# BBB_Headers.net
KiCad netlist of a schematic drawn in Altium Designer
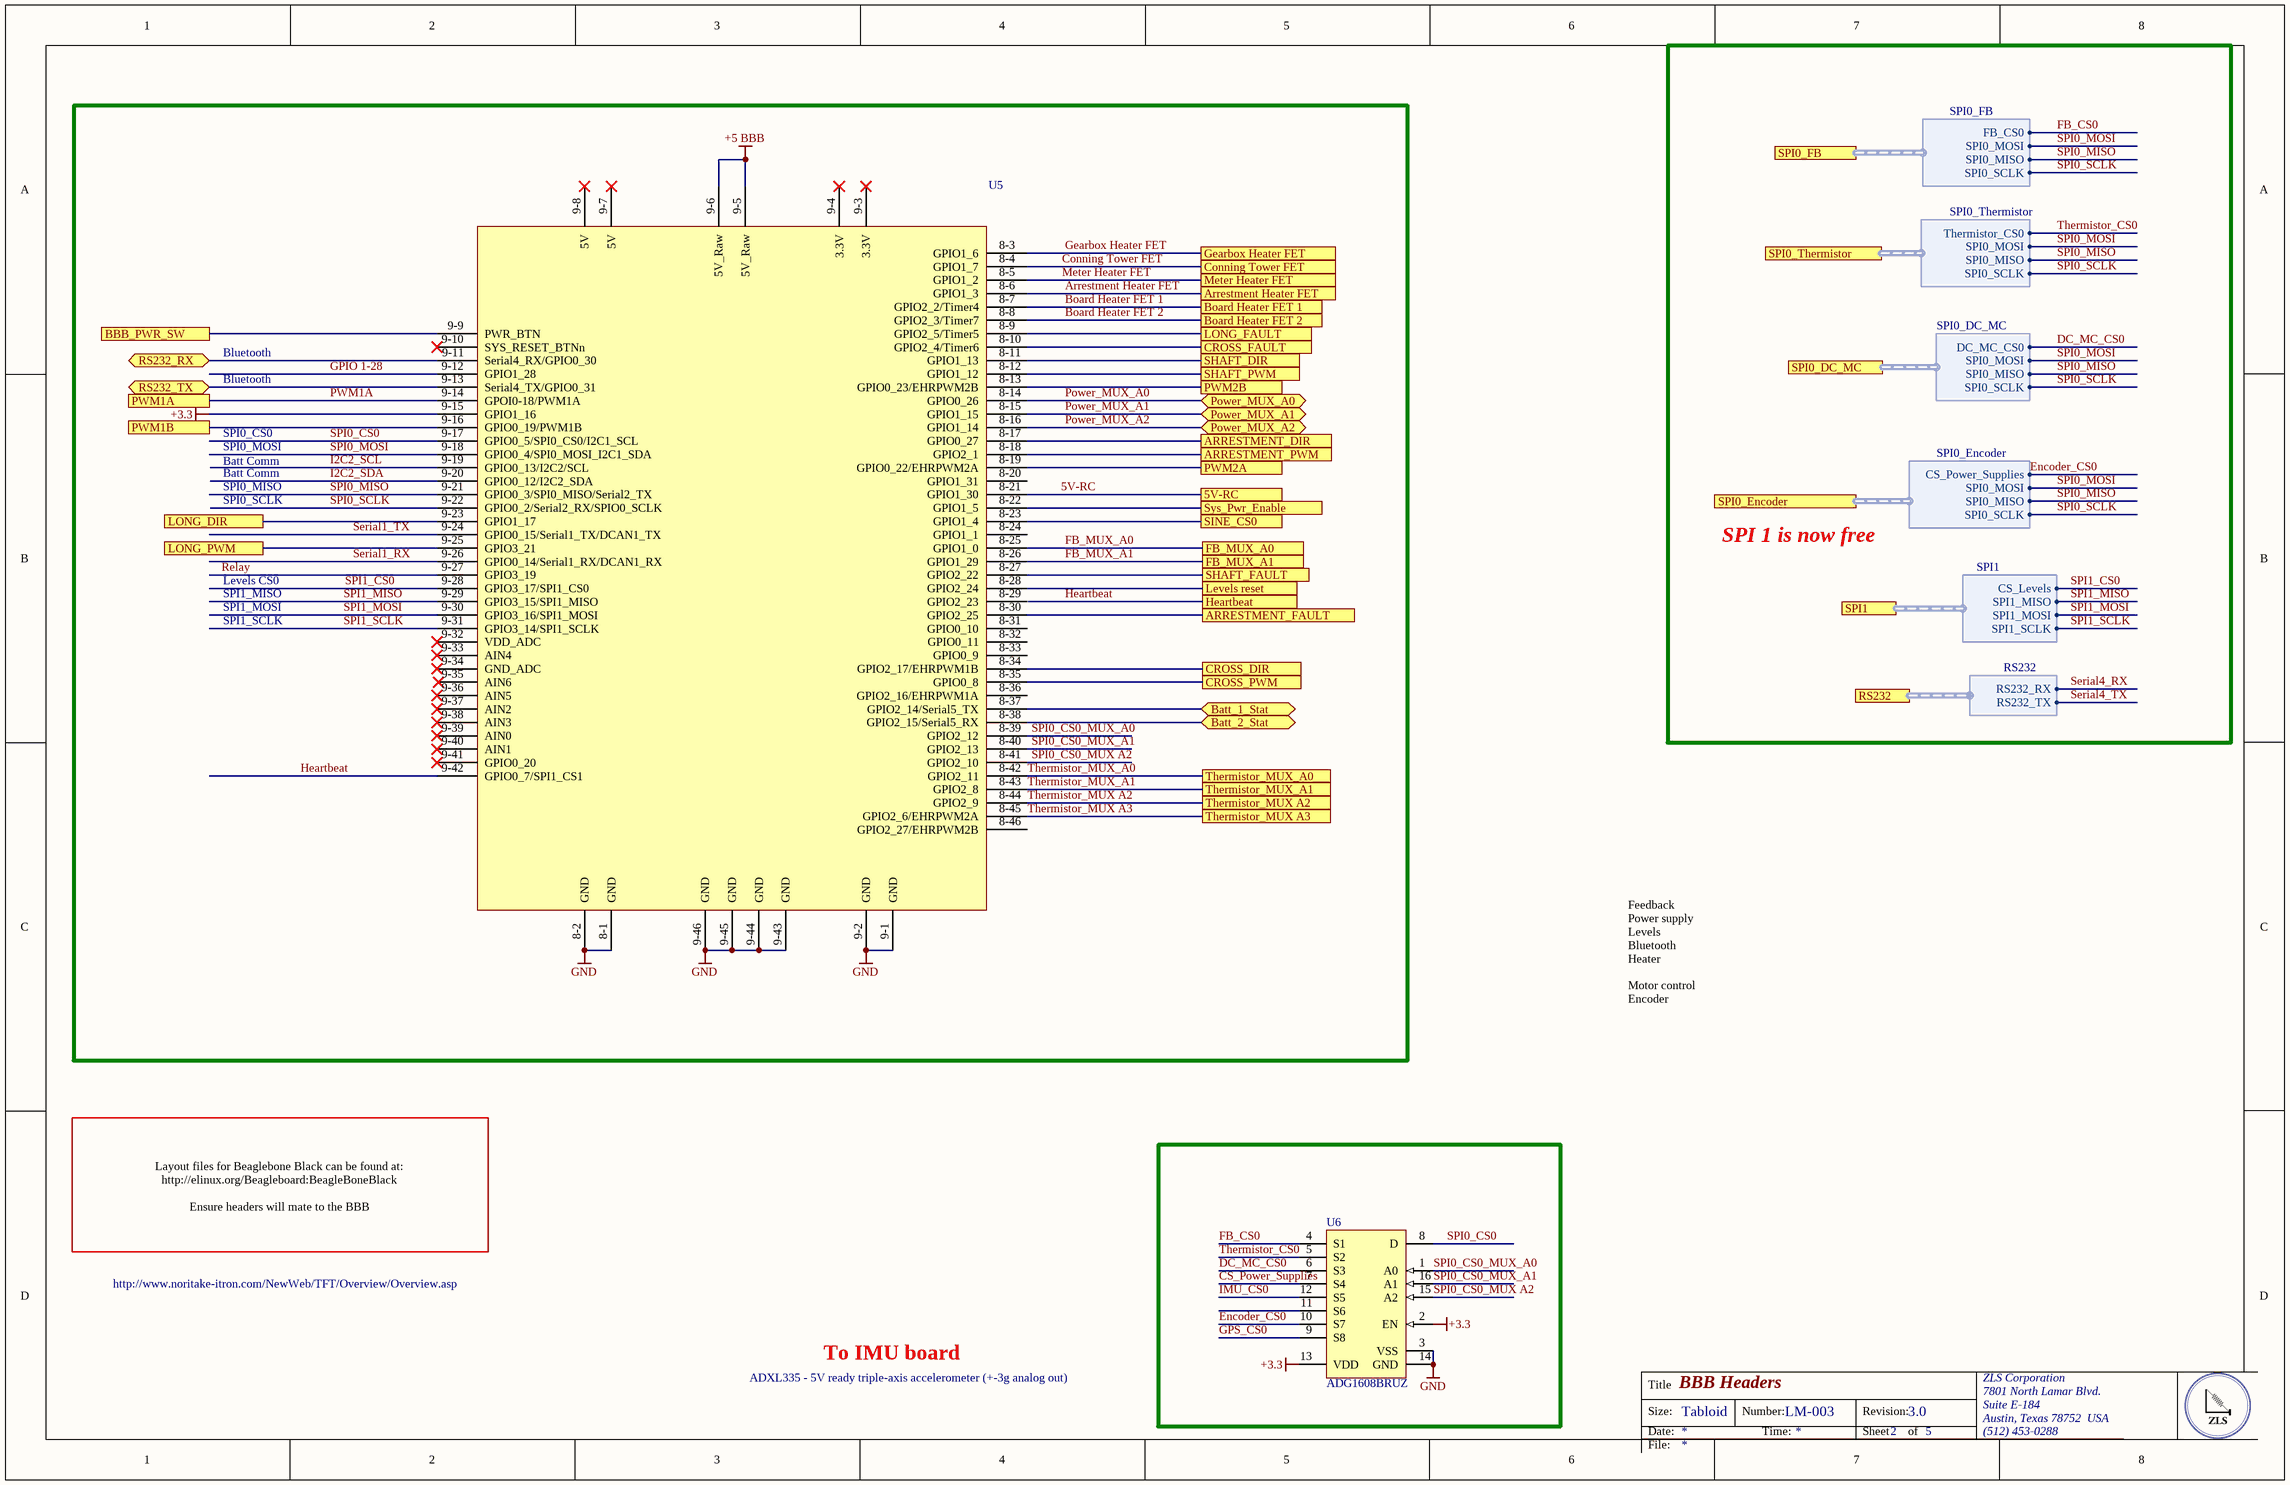
[diagram p0: BBB Headers.SchDoc]

(export (version "E")
  (design (tool "Eeschema 10.0.6"))
  (components
    (comp (ref "U5")
      (value "BBB")
      (footprint "Beaglebone Black")
      (description "Beaglebone Black")
      (fields
        (field (name "MANUFACTURER") "Molex, LLC")
        (field (name "MANUFACTURER PART NUMBER") "0010897462")
      )
      (libsource (lib "ZLS_Schematic_lib") (part "Beaglebone_Black"))
    )
    (comp (ref "U6")
      (value "ADG1608BRUZ")
      (footprint "ADI-RU-16_M")
      (description "4.5 Ohm Ron, 8-Channel +/-5 V,+12 V, +5 V and +3.3 V Multiplexer, 16-pin SOP (RU-16), Tube")
      (fields (field (name "MANUFACTURER") "Analog Devices"))
      (libsource (lib "Altium Content Vault") (part "ADI-ADG1608-RU-16"))
    )
  )
  (nets
    (net (code "7") (name "+3.3") (class "Default")
      (node (ref "U5") (pin "9-15") (pinfunction "GPIO1_16_9-15") (pintype "passive"))
      (node (ref "U6") (pin "13") (pinfunction "VDD_13") (pintype "power_in"))
      (node (ref "U6") (pin "2") (pinfunction "EN_2") (pintype "input"))
    )
    (net (code "8") (name "+5 BBB") (class "Default")
      (node (ref "U5") (pin "9-5") (pinfunction "5V_Raw_9-5") (pintype "passive"))
      (node (ref "U5") (pin "9-6") (pinfunction "5V_Raw_9-6") (pintype "passive"))
    )
    (net (code "9") (name "/5V-RC") (class "Default")
      (node (ref "U5") (pin "8-21") (pinfunction "GPIO1_30_8-21") (pintype "passive"))
    )
    (net (code "10") (name "/ARRESTMENT_DIR") (class "Default")
      (node (ref "U5") (pin "8-17") (pinfunction "GPIO0_27_8-17") (pintype "passive"))
    )
    (net (code "11") (name "/ARRESTMENT_FAULT") (class "Default")
      (node (ref "U5") (pin "8-30") (pinfunction "GPIO2_25_8-30") (pintype "passive"))
    )
    (net (code "12") (name "/ARRESTMENT_PWM") (class "Default")
      (node (ref "U5") (pin "8-18") (pinfunction "GPIO2_1_8-18") (pintype "passive"))
    )
    (net (code "13") (name "/Arrestment Heater FET") (class "Default")
      (node (ref "U5") (pin "8-6") (pinfunction "GPIO1_3_8-6") (pintype "passive"))
    )
    (net (code "14") (name "/BBB_PWR_SW") (class "Default")
      (node (ref "U5") (pin "9-9") (pinfunction "PWR_BTN_9-9") (pintype "passive"))
    )
    (net (code "15") (name "/Batt_1_Stat") (class "Default")
      (node (ref "U5") (pin "8-37") (pinfunction "GPIO2_14/Serial5_TX_8-37") (pintype "passive"))
    )
    (net (code "16") (name "/Batt_2_Stat") (class "Default")
      (node (ref "U5") (pin "8-38") (pinfunction "GPIO2_15/Serial5_RX_8-38") (pintype "passive"))
    )
    (net (code "17") (name "/Board Heater FET 1") (class "Default")
      (node (ref "U5") (pin "8-7") (pinfunction "GPIO2_2/Timer4_8-7") (pintype "passive"))
    )
    (net (code "18") (name "/Board Heater FET 2") (class "Default")
      (node (ref "U5") (pin "8-8") (pinfunction "GPIO2_3/Timer7_8-8") (pintype "passive"))
    )
    (net (code "19") (name "/CROSS_DIR") (class "Default")
      (node (ref "U5") (pin "8-34") (pinfunction "GPIO2_17/EHRPWM1B_8-34") (pintype "passive"))
    )
    (net (code "20") (name "/CROSS_FAULT") (class "Default")
      (node (ref "U5") (pin "8-10") (pinfunction "GPIO2_4/Timer6_8-10") (pintype "passive"))
    )
    (net (code "21") (name "/CROSS_PWM") (class "Default")
      (node (ref "U5") (pin "8-35") (pinfunction "GPIO0_8_8-35") (pintype "passive"))
    )
    (net (code "22") (name "/CS_Power_Supplies") (class "Default")
      (node (ref "U6") (pin "7") (pinfunction "S4_7") (pintype "passive"))
    )
    (net (code "23") (name "/Conning Tower FET") (class "Default")
      (node (ref "U5") (pin "8-4") (pinfunction "GPIO1_7_8-4") (pintype "passive"))
    )
    (net (code "24") (name "/DC_MC_CS0") (class "Default")
      (node (ref "U6") (pin "6") (pinfunction "S3_6") (pintype "passive"))
    )
    (net (code "25") (name "/Encoder_CS0") (class "Default")
      (node (ref "U6") (pin "10") (pinfunction "S7_10") (pintype "passive"))
    )
    (net (code "26") (name "/FB_CS0") (class "Default")
      (node (ref "U6") (pin "4") (pinfunction "S1_4") (pintype "passive"))
    )
    (net (code "27") (name "/FB_MUX_A0") (class "Default")
      (node (ref "U5") (pin "8-25") (pinfunction "GPIO1_0_8-25") (pintype "passive"))
    )
    (net (code "28") (name "/FB_MUX_A1") (class "Default")
      (node (ref "U5") (pin "8-26") (pinfunction "GPIO1_29_8-26") (pintype "passive"))
    )
    (net (code "29") (name "/GPIO 1-28") (class "Default")
      (node (ref "U5") (pin "9-12") (pinfunction "GPIO1_28_9-12") (pintype "passive"))
    )
    (net (code "30") (name "/GPS_CS0") (class "Default")
      (node (ref "U6") (pin "9") (pinfunction "S8_9") (pintype "passive"))
    )
    (net (code "31") (name "/Gearbox Heater FET") (class "Default")
      (node (ref "U5") (pin "8-3") (pinfunction "GPIO1_6_8-3") (pintype "passive"))
    )
    (net (code "32") (name "/Heartbeat") (class "Default")
      (node (ref "U5") (pin "9-42") (pinfunction "GPIO0_7/SPI1_CS1_9-42") (pintype "passive"))
    )
    (net (code "33") (name "/I2C2_SCL") (class "Default")
      (node (ref "U5") (pin "9-19") (pinfunction "GPIO0_13/I2C2/SCL_9-19") (pintype "passive"))
    )
    (net (code "34") (name "/I2C2_SDA") (class "Default")
      (node (ref "U5") (pin "9-20") (pinfunction "GPIO0_12/I2C2_SDA_9-20") (pintype "passive"))
    )
    (net (code "35") (name "/IMU_CS0") (class "Default")
      (node (ref "U6") (pin "12") (pinfunction "S5_12") (pintype "passive"))
    )
    (net (code "36") (name "/LONG_DIR") (class "Default")
      (node (ref "U5") (pin "9-23") (pinfunction "GPIO1_17_9-23") (pintype "passive"))
    )
    (net (code "37") (name "/LONG_FAULT") (class "Default")
      (node (ref "U5") (pin "8-9") (pinfunction "GPIO2_5/Timer5_8-9") (pintype "passive"))
    )
    (net (code "38") (name "/LONG_PWM") (class "Default")
      (node (ref "U5") (pin "9-25") (pinfunction "GPIO3_21_9-25") (pintype "passive"))
    )
    (net (code "39") (name "/Levels reset") (class "Default")
      (node (ref "U5") (pin "8-28") (pinfunction "GPIO2_24_8-28") (pintype "passive"))
    )
    (net (code "40") (name "/Meter Heater FET") (class "Default")
      (node (ref "U5") (pin "8-5") (pinfunction "GPIO1_2_8-5") (pintype "passive"))
    )
    (net (code "41") (name "/PWM1A") (class "Default")
      (node (ref "U5") (pin "9-14") (pinfunction "GPOI0-18/PWM1A_9-14") (pintype "passive"))
    )
    (net (code "42") (name "/PWM1B") (class "Default")
      (node (ref "U5") (pin "9-16") (pinfunction "GPIO0_19/PWM1B_9-16") (pintype "passive"))
    )
    (net (code "43") (name "/PWM2A") (class "Default")
      (node (ref "U5") (pin "8-19") (pinfunction "GPIO0_22/EHRPWM2A_8-19") (pintype "passive"))
    )
    (net (code "44") (name "/PWM2B") (class "Default")
      (node (ref "U5") (pin "8-13") (pinfunction "GPIO0_23/EHRPWM2B_8-13") (pintype "passive"))
    )
    (net (code "45") (name "/Power_MUX_A0") (class "Default")
      (node (ref "U5") (pin "8-14") (pinfunction "GPIO0_26_8-14") (pintype "passive"))
    )
    (net (code "46") (name "/Power_MUX_A1") (class "Default")
      (node (ref "U5") (pin "8-15") (pinfunction "GPIO1_15_8-15") (pintype "passive"))
    )
    (net (code "47") (name "/Power_MUX_A2") (class "Default")
      (node (ref "U5") (pin "8-16") (pinfunction "GPIO1_14_8-16") (pintype "passive"))
    )
    (net (code "48") (name "/RS232_RX") (class "Default")
      (node (ref "U5") (pin "9-11") (pinfunction "Serial4_RX/GPIO0_30_9-11") (pintype "passive"))
    )
    (net (code "49") (name "/RS232_TX") (class "Default")
      (node (ref "U5") (pin "9-13") (pinfunction "Serial4_TX/GPIO0_31_9-13") (pintype "passive"))
    )
    (net (code "50") (name "/Relay") (class "Default")
      (node (ref "U5") (pin "9-27") (pinfunction "GPIO3_19_9-27") (pintype "passive"))
    )
    (net (code "51") (name "/SHAFT_DIR") (class "Default")
      (node (ref "U5") (pin "8-11") (pinfunction "GPIO1_13_8-11") (pintype "passive"))
    )
    (net (code "52") (name "/SHAFT_FAULT") (class "Default")
      (node (ref "U5") (pin "8-27") (pinfunction "GPIO2_22_8-27") (pintype "passive"))
    )
    (net (code "53") (name "/SHAFT_PWM") (class "Default")
      (node (ref "U5") (pin "8-12") (pinfunction "GPIO1_12_8-12") (pintype "passive"))
    )
    (net (code "54") (name "/SINE_CS0") (class "Default")
      (node (ref "U5") (pin "8-23") (pinfunction "GPIO1_4_8-23") (pintype "passive"))
    )
    (net (code "55") (name "/SPI0_CS0") (class "Default")
      (node (ref "U5") (pin "9-17") (pinfunction "GPIO0_5/SPI0_CS0/I2C1_SCL_9-17") (pintype "passive"))
      (node (ref "U6") (pin "8") (pinfunction "D_8") (pintype "passive"))
    )
    (net (code "56") (name "/SPI0_CS0_MUX A2") (class "Default")
      (node (ref "U5") (pin "8-41") (pinfunction "GPIO2_10_8-41") (pintype "passive"))
      (node (ref "U6") (pin "15") (pinfunction "A2_15") (pintype "input"))
    )
    (net (code "57") (name "/SPI0_CS0_MUX_A0") (class "Default")
      (node (ref "U5") (pin "8-39") (pinfunction "GPIO2_12_8-39") (pintype "passive"))
      (node (ref "U6") (pin "1") (pinfunction "A0_1") (pintype "input"))
    )
    (net (code "58") (name "/SPI0_CS0_MUX_A1") (class "Default")
      (node (ref "U5") (pin "8-40") (pinfunction "GPIO2_13_8-40") (pintype "passive"))
      (node (ref "U6") (pin "16") (pinfunction "A1_16") (pintype "input"))
    )
    (net (code "59") (name "/SPI0_MISO") (class "Default")
      (node (ref "U5") (pin "9-21") (pinfunction "GPIO0_3/SPI0_MISO/Serial2_TX_9-21") (pintype "passive"))
    )
    (net (code "60") (name "/SPI0_MOSI") (class "Default")
      (node (ref "U5") (pin "9-18") (pinfunction "GPIO0_4/SPI0_MOSI_I2C1_SDA_9-18") (pintype "passive"))
    )
    (net (code "61") (name "/SPI0_SCLK") (class "Default")
      (node (ref "U5") (pin "9-22") (pinfunction "GPIO0_2/Serial2_RX/SPIO0_SCLK_9-22") (pintype "passive"))
    )
    (net (code "62") (name "/SPI1_CS0") (class "Default")
      (node (ref "U5") (pin "9-28") (pinfunction "GPIO3_17/SPI1_CS0_9-28") (pintype "passive"))
    )
    (net (code "63") (name "/SPI1_MISO") (class "Default")
      (node (ref "U5") (pin "9-29") (pinfunction "GPIO3_15/SPI1_MISO_9-29") (pintype "passive"))
    )
    (net (code "64") (name "/SPI1_MOSI") (class "Default")
      (node (ref "U5") (pin "9-30") (pinfunction "GPIO3_16/SPI1_MOSI_9-30") (pintype "passive"))
    )
    (net (code "65") (name "/SPI1_SCLK") (class "Default")
      (node (ref "U5") (pin "9-31") (pinfunction "GPIO3_14/SPI1_SCLK_9-31") (pintype "passive"))
    )
    (net (code "66") (name "/Serial1_RX") (class "Default")
      (node (ref "U5") (pin "9-26") (pinfunction "GPIO0_14/Serial1_RX/DCAN1_RX_9-26") (pintype "passive"))
    )
    (net (code "67") (name "/Serial1_TX") (class "Default")
      (node (ref "U5") (pin "9-24") (pinfunction "GPIO0_15/Serial1_TX/DCAN1_TX_9-24") (pintype "passive"))
    )
    (net (code "70") (name "/Sys_Pwr_Enable") (class "Default")
      (node (ref "U5") (pin "8-22") (pinfunction "GPIO1_5_8-22") (pintype "passive"))
    )
    (net (code "71") (name "/Thermistor_CS0") (class "Default")
      (node (ref "U6") (pin "5") (pinfunction "S2_5") (pintype "passive"))
    )
    (net (code "72") (name "/Thermistor_MUX A2") (class "Default")
      (node (ref "U5") (pin "8-44") (pinfunction "GPIO2_9_8-44") (pintype "passive"))
    )
    (net (code "73") (name "/Thermistor_MUX A3") (class "Default")
      (node (ref "U5") (pin "8-45") (pinfunction "GPIO2_6/EHRPWM2A_8-45") (pintype "passive"))
    )
    (net (code "74") (name "/Thermistor_MUX_A0") (class "Default")
      (node (ref "U5") (pin "8-42") (pinfunction "GPIO2_11_8-42") (pintype "passive"))
    )
    (net (code "75") (name "/Thermistor_MUX_A1") (class "Default")
      (node (ref "U5") (pin "8-43") (pinfunction "GPIO2_8_8-43") (pintype "passive"))
    )
    (net (code "82") (name "GND") (class "Default")
      (node (ref "U5") (pin "8-1") (pinfunction "GND_8-1") (pintype "passive"))
      (node (ref "U5") (pin "8-2") (pinfunction "GND_8-2") (pintype "passive"))
      (node (ref "U5") (pin "9-1") (pinfunction "GND_9-1") (pintype "passive"))
      (node (ref "U5") (pin "9-2") (pinfunction "GND_9-2") (pintype "passive"))
      (node (ref "U5") (pin "9-43") (pinfunction "GND_9-43") (pintype "passive"))
      (node (ref "U5") (pin "9-44") (pinfunction "GND_9-44") (pintype "passive"))
      (node (ref "U5") (pin "9-45") (pinfunction "GND_9-45") (pintype "passive"))
      (node (ref "U5") (pin "9-46") (pinfunction "GND_9-46") (pintype "passive"))
      (node (ref "U6") (pin "14") (pinfunction "GND_14") (pintype "power_in"))
      (node (ref "U6") (pin "3") (pinfunction "VSS_3") (pintype "power_in"))
    )
    (net (code "83") (name "unconnected-(U5-3.3V-Pad9-3)") (class "Default")
      (node (ref "U5") (pin "9-3") (pinfunction "3.3V_9-3") (pintype "passive+no_connect"))
    )
    (net (code "84") (name "unconnected-(U5-3.3V-Pad9-4)") (class "Default")
      (node (ref "U5") (pin "9-4") (pinfunction "3.3V_9-4") (pintype "passive+no_connect"))
    )
    (net (code "85") (name "unconnected-(U5-5V-Pad9-7)") (class "Default")
      (node (ref "U5") (pin "9-7") (pinfunction "5V_9-7") (pintype "passive+no_connect"))
    )
    (net (code "86") (name "unconnected-(U5-5V-Pad9-8)") (class "Default")
      (node (ref "U5") (pin "9-8") (pinfunction "5V_9-8") (pintype "passive+no_connect"))
    )
    (net (code "87") (name "unconnected-(U5-AIN0-Pad9-39)") (class "Default")
      (node (ref "U5") (pin "9-39") (pinfunction "AIN0_9-39") (pintype "passive+no_connect"))
    )
    (net (code "88") (name "unconnected-(U5-AIN1-Pad9-40)") (class "Default")
      (node (ref "U5") (pin "9-40") (pinfunction "AIN1_9-40") (pintype "passive+no_connect"))
    )
    (net (code "89") (name "unconnected-(U5-AIN2-Pad9-37)") (class "Default")
      (node (ref "U5") (pin "9-37") (pinfunction "AIN2_9-37") (pintype "passive+no_connect"))
    )
    (net (code "90") (name "unconnected-(U5-AIN3-Pad9-38)") (class "Default")
      (node (ref "U5") (pin "9-38") (pinfunction "AIN3_9-38") (pintype "passive+no_connect"))
    )
    (net (code "91") (name "unconnected-(U5-AIN4-Pad9-33)") (class "Default")
      (node (ref "U5") (pin "9-33") (pinfunction "AIN4_9-33") (pintype "passive+no_connect"))
    )
    (net (code "92") (name "unconnected-(U5-AIN5-Pad9-36)") (class "Default")
      (node (ref "U5") (pin "9-36") (pinfunction "AIN5_9-36") (pintype "passive+no_connect"))
    )
    (net (code "93") (name "unconnected-(U5-AIN6-Pad9-35)") (class "Default")
      (node (ref "U5") (pin "9-35") (pinfunction "AIN6_9-35") (pintype "passive"))
    )
    (net (code "94") (name "unconnected-(U5-GND_ADC-Pad9-34)") (class "Default")
      (node (ref "U5") (pin "9-34") (pinfunction "GND_ADC_9-34") (pintype "passive+no_connect"))
    )
    (net (code "95") (name "unconnected-(U5-GPIO0_9-Pad8-33)") (class "Default")
      (node (ref "U5") (pin "8-33") (pinfunction "GPIO0_9_8-33") (pintype "passive"))
    )
    (net (code "96") (name "unconnected-(U5-GPIO0_10-Pad8-31)") (class "Default")
      (node (ref "U5") (pin "8-31") (pinfunction "GPIO0_10_8-31") (pintype "passive"))
    )
    (net (code "97") (name "unconnected-(U5-GPIO0_11-Pad8-32)") (class "Default")
      (node (ref "U5") (pin "8-32") (pinfunction "GPIO0_11_8-32") (pintype "passive"))
    )
    (net (code "98") (name "unconnected-(U5-GPIO0_20-Pad9-41)") (class "Default")
      (node (ref "U5") (pin "9-41") (pinfunction "GPIO0_20_9-41") (pintype "passive+no_connect"))
    )
    (net (code "99") (name "unconnected-(U5-GPIO1_1-Pad8-24)") (class "Default")
      (node (ref "U5") (pin "8-24") (pinfunction "GPIO1_1_8-24") (pintype "passive"))
    )
    (net (code "100") (name "unconnected-(U5-GPIO1_31-Pad8-20)") (class "Default")
      (node (ref "U5") (pin "8-20") (pinfunction "GPIO1_31_8-20") (pintype "passive"))
    )
    (net (code "101") (name "unconnected-(U5-GPIO2_16{slash}EHRPWM1A-Pad8-36)") (class "Default")
      (node (ref "U5") (pin "8-36") (pinfunction "GPIO2_16/EHRPWM1A_8-36") (pintype "passive"))
    )
    (net (code "102") (name "unconnected-(U5-GPIO2_23-Pad8-29)") (class "Default")
      (node (ref "U5") (pin "8-29") (pinfunction "GPIO2_23_8-29") (pintype "passive"))
    )
    (net (code "103") (name "unconnected-(U5-GPIO2_27{slash}EHRPWM2B-Pad8-46)") (class "Default")
      (node (ref "U5") (pin "8-46") (pinfunction "GPIO2_27/EHRPWM2B_8-46") (pintype "passive"))
    )
    (net (code "104") (name "unconnected-(U5-SYS_RESET_BTNn-Pad9-10)") (class "Default")
      (node (ref "U5") (pin "9-10") (pinfunction "SYS_RESET_BTNn_9-10") (pintype "passive+no_connect"))
    )
    (net (code "105") (name "unconnected-(U5-VDD_ADC-Pad9-32)") (class "Default")
      (node (ref "U5") (pin "9-32") (pinfunction "VDD_ADC_9-32") (pintype "passive+no_connect"))
    )
    (net (code "106") (name "unconnected-(U6-S6-Pad11)") (class "Default")
      (node (ref "U6") (pin "11") (pinfunction "S6_11") (pintype "passive"))
    )
  )
)
